# IMX425_MB.net
KiCad netlist of a schematic drawn in Altium Designer
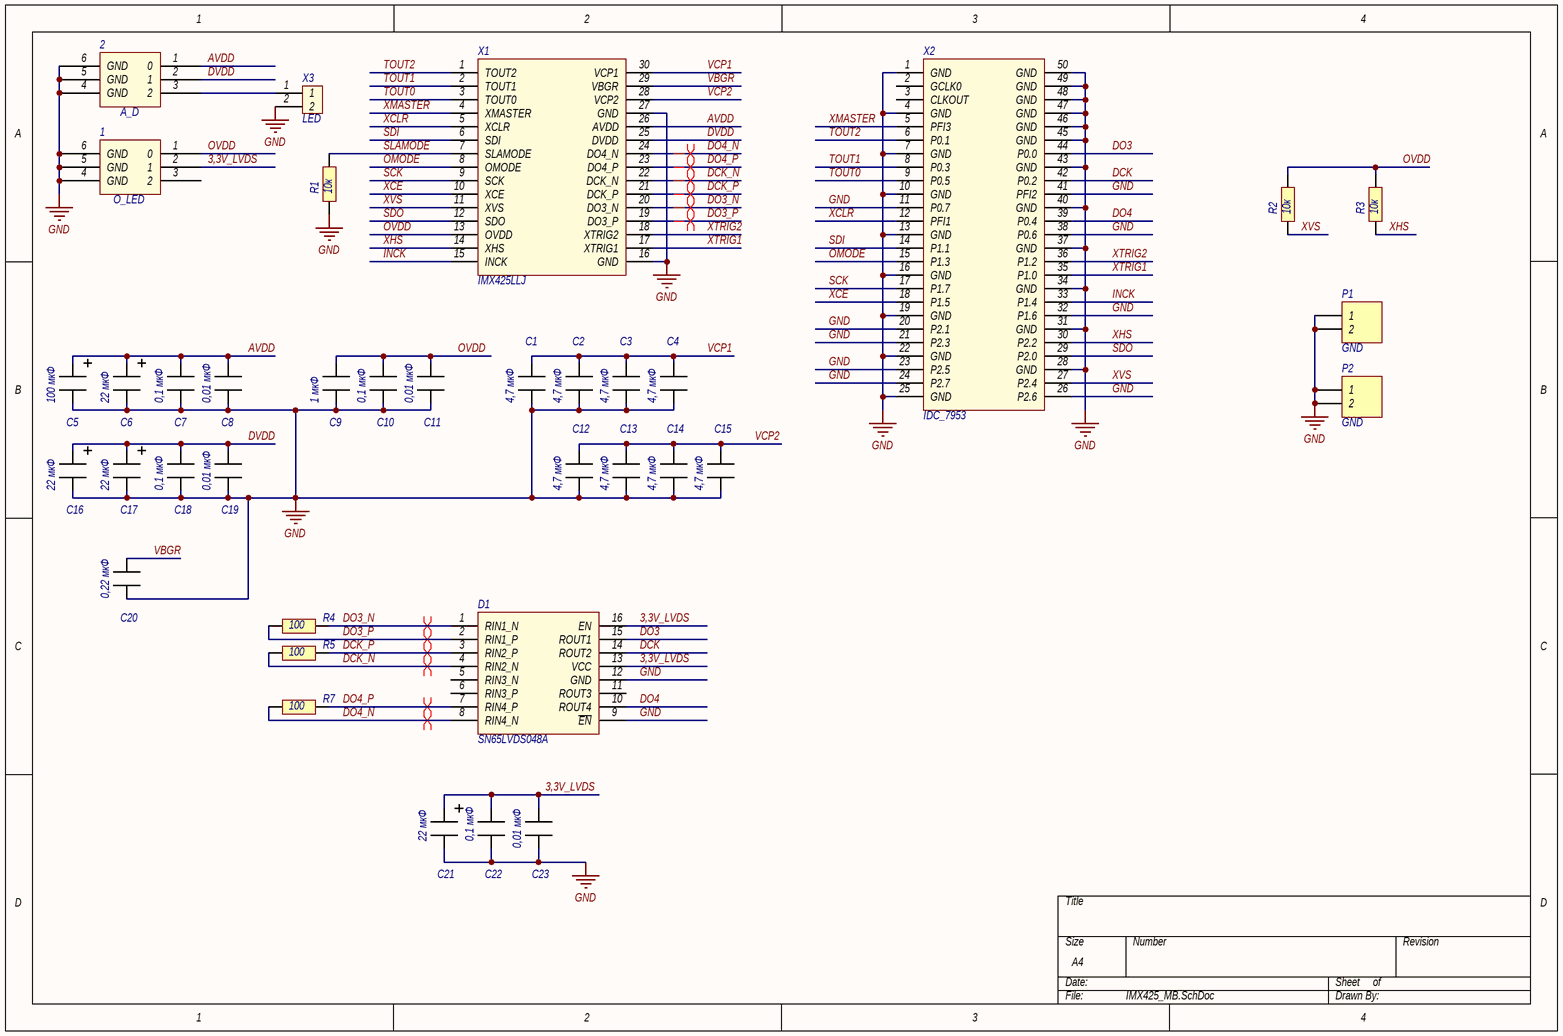
[diagram p0: IMX425_MB.SchDoc]

(export (version "E")
  (design (tool "Eeschema 10.0.6"))
  (components
    (comp (ref "1") (value "O_LED") (footprint "POWER") (libsource (lib "Schlib") (part "POWER")))
    (comp (ref "2") (value "A_D") (footprint "POWER") (libsource (lib "Schlib") (part "POWER")))
    (comp (ref "C1") (value "4,7 мкФ") (footprint "CAP_SMALL") (libsource (lib "Schlib") (part "CAP_SMALL")))
    (comp (ref "C2") (value "4,7 мкФ") (footprint "CAP_SMALL") (libsource (lib "Schlib") (part "CAP_SMALL")))
    (comp (ref "C3") (value "4,7 мкФ") (footprint "CAP_SMALL") (libsource (lib "Schlib") (part "CAP_SMALL")))
    (comp (ref "C4") (value "4,7 мкФ") (footprint "CAP_SMALL") (libsource (lib "Schlib") (part "CAP_SMALL")))
    (comp (ref "C5")
      (value "100 мкФ")
      (footprint "Cap_0612_electrolitic")
      (libsource (lib "Schlib") (part "Cap_electrolotoc_0612"))
    )
    (comp (ref "C6")
      (value "22 мкФ")
      (footprint "Cap_0511_electrolitic")
      (libsource (lib "Schlib") (part "Cap_electrolotoc_0511"))
    )
    (comp (ref "C7") (value "0,1 мкФ") (footprint "CAP_SMALL") (libsource (lib "Schlib") (part "CAP_SMALL")))
    (comp (ref "C8") (value "0,01 мкФ") (footprint "CAP_SMALL") (libsource (lib "Schlib") (part "CAP_SMALL")))
    (comp (ref "C9") (value "1 мкФ") (footprint "CAP_SMALL") (libsource (lib "Schlib") (part "CAP_SMALL")))
    (comp (ref "C10") (value "0,1 мкФ") (footprint "CAP_SMALL") (libsource (lib "Schlib") (part "CAP_SMALL")))
    (comp (ref "C11")
      (value "0,01 мкФ")
      (footprint "CAP_SMALL")
      (libsource (lib "Schlib") (part "CAP_SMALL"))
    )
    (comp (ref "C12") (value "4,7 мкФ") (footprint "CAP_SMALL") (libsource (lib "Schlib") (part "CAP_SMALL")))
    (comp (ref "C13") (value "4,7 мкФ") (footprint "CAP_SMALL") (libsource (lib "Schlib") (part "CAP_SMALL")))
    (comp (ref "C14") (value "4,7 мкФ") (footprint "CAP_SMALL") (libsource (lib "Schlib") (part "CAP_SMALL")))
    (comp (ref "C15") (value "4,7 мкФ") (footprint "CAP_SMALL") (libsource (lib "Schlib") (part "CAP_SMALL")))
    (comp (ref "C16")
      (value "22 мкФ")
      (footprint "Cap_0511_electrolitic")
      (libsource (lib "Schlib") (part "Cap_electrolotoc_0511"))
    )
    (comp (ref "C17")
      (value "22 мкФ")
      (footprint "Cap_0511_electrolitic")
      (libsource (lib "Schlib") (part "Cap_electrolotoc_0511"))
    )
    (comp (ref "C18") (value "0,1 мкФ") (footprint "CAP_SMALL") (libsource (lib "Schlib") (part "CAP_SMALL")))
    (comp (ref "C19")
      (value "0,01 мкФ")
      (footprint "CAP_SMALL")
      (libsource (lib "Schlib") (part "CAP_SMALL"))
    )
    (comp (ref "C20")
      (value "0,22 мкФ")
      (footprint "CAP_SMALL")
      (libsource (lib "Schlib") (part "CAP_SMALL"))
    )
    (comp (ref "C21")
      (value "22 мкФ")
      (footprint "Cap_0511_electrolitic")
      (libsource (lib "Schlib") (part "Cap_electrolotoc_0511"))
    )
    (comp (ref "C22") (value "0,1 мкФ") (footprint "CAP_SMALL") (libsource (lib "Schlib") (part "CAP_SMALL")))
    (comp (ref "C23")
      (value "0,01 мкФ")
      (footprint "CAP_SMALL")
      (libsource (lib "Schlib") (part "CAP_SMALL"))
    )
    (comp (ref "D1")
      (value "SN65LVDS048A")
      (footprint "SN65LVDS048A (4LVDS)")
      (libsource (lib "Schlib") (part "SN65LVDS048A (4LVDS)"))
    )
    (comp (ref "P1")
      (value "GND")
      (footprint "HDR1X2")
      (description "Header, 2-Pin")
      (fields (field (name "PUBLISHER") "Altium Limited"))
      (libsource (lib "Miscellaneous Connectors") (part "Header 2"))
    )
    (comp (ref "P2")
      (value "GND")
      (footprint "HDR1X2")
      (description "Header, 2-Pin")
      (fields (field (name "PUBLISHER") "Altium Limited"))
      (libsource (lib "Miscellaneous Connectors") (part "Header 2"))
    )
    (comp (ref "R1") (value "10к") (footprint "RES") (libsource (lib "Schlib") (part "RES")))
    (comp (ref "R2") (value "10к") (footprint "RES") (libsource (lib "Schlib") (part "RES")))
    (comp (ref "R3") (value "10к") (footprint "RES") (libsource (lib "Schlib") (part "RES")))
    (comp (ref "R4") (value "100") (footprint "RES") (libsource (lib "") (part "RES_1")))
    (comp (ref "R5") (value "100") (footprint "RES") (libsource (lib "") (part "RES_1")))
    (comp (ref "R7") (value "100") (footprint "RES") (libsource (lib "") (part "RES_1")))
    (comp (ref "X1")
      (value "IMX425LLJ")
      (footprint "IMX425LLJ_MEZ")
      (libsource (lib "VPL") (part "IMX425LLJ_MEZ"))
    )
    (comp (ref "X2") (value "IDC_7953") (footprint "IDC_7953") (libsource (lib "VPL") (part "IDC_7953")))
    (comp (ref "X3") (value "LED") (footprint "KLEMMNIK_2") (libsource (lib "Schlib") (part "KLEMMNIK_2")))
  )
  (nets
    (net (code "1") (name "/3,3V_LVDS") (class "Default")
      (node (ref "1") (pin "2") (pinfunction "1_2") (pintype "passive"))
      (node (ref "C21") (pin "1") (pinfunction "1_1") (pintype "passive"))
      (node (ref "C22") (pin "2") (pinfunction "2_2") (pintype "passive"))
      (node (ref "C23") (pin "2") (pinfunction "2_2") (pintype "passive"))
      (node (ref "D1") (pin "13") (pinfunction "VCC_13") (pintype "passive"))
      (node (ref "D1") (pin "16") (pinfunction "EN_16") (pintype "passive"))
    )
    (net (code "2") (name "/AVDD") (class "Default")
      (node (ref "2") (pin "1") (pinfunction "0_1") (pintype "passive"))
      (node (ref "C5") (pin "1") (pinfunction "1_1") (pintype "passive"))
      (node (ref "C6") (pin "1") (pinfunction "1_1") (pintype "passive"))
      (node (ref "C7") (pin "1") (pinfunction "1_1") (pintype "passive"))
      (node (ref "C8") (pin "1") (pinfunction "1_1") (pintype "passive"))
      (node (ref "X1") (pin "26") (pinfunction "AVDD_26") (pintype "passive"))
    )
    (net (code "3") (name "/DCK") (class "Default")
      (node (ref "D1") (pin "14") (pinfunction "ROUT2_14") (pintype "passive"))
      (node (ref "X2") (pin "42") (pinfunction "P0.2_42") (pintype "passive"))
    )
    (net (code "4") (name "/DCK_N") (class "Default")
      (node (ref "D1") (pin "4") (pinfunction "RIN2_N_4") (pintype "passive"))
      (node (ref "R5") (pin "2") (pinfunction "2_2") (pintype "passive"))
      (node (ref "X1") (pin "22") (pinfunction "DCK_N_22") (pintype "passive"))
    )
    (net (code "5") (name "/DCK_P") (class "Default")
      (node (ref "D1") (pin "3") (pinfunction "RIN2_P_3") (pintype "passive"))
      (node (ref "R5") (pin "1") (pinfunction "1_1") (pintype "passive"))
      (node (ref "X1") (pin "21") (pinfunction "DCK_P_21") (pintype "passive"))
    )
    (net (code "6") (name "/DO3") (class "Default")
      (node (ref "D1") (pin "15") (pinfunction "ROUT1_15") (pintype "passive"))
      (node (ref "X2") (pin "44") (pinfunction "P0.0_44") (pintype "passive"))
    )
    (net (code "7") (name "/DO3_N") (class "Default")
      (node (ref "D1") (pin "1") (pinfunction "RIN1_N_1") (pintype "passive"))
      (node (ref "R4") (pin "1") (pinfunction "1_1") (pintype "passive"))
      (node (ref "X1") (pin "20") (pinfunction "DO3_N_20") (pintype "passive"))
    )
    (net (code "8") (name "/DO3_P") (class "Default")
      (node (ref "D1") (pin "2") (pinfunction "RIN1_P_2") (pintype "passive"))
      (node (ref "R4") (pin "2") (pinfunction "2_2") (pintype "passive"))
      (node (ref "X1") (pin "19") (pinfunction "DO3_P_19") (pintype "passive"))
    )
    (net (code "9") (name "/DO4") (class "Default")
      (node (ref "D1") (pin "10") (pinfunction "ROUT4_10") (pintype "passive"))
      (node (ref "X2") (pin "39") (pinfunction "P0.4_39") (pintype "passive"))
    )
    (net (code "10") (name "/DO4_N") (class "Default")
      (node (ref "D1") (pin "8") (pinfunction "RIN4_N_8") (pintype "passive"))
      (node (ref "R7") (pin "2") (pinfunction "2_2") (pintype "passive"))
      (node (ref "X1") (pin "24") (pinfunction "DO4_N_24") (pintype "passive"))
    )
    (net (code "11") (name "/DO4_P") (class "Default")
      (node (ref "D1") (pin "7") (pinfunction "RIN4_P_7") (pintype "passive"))
      (node (ref "R7") (pin "1") (pinfunction "1_1") (pintype "passive"))
      (node (ref "X1") (pin "23") (pinfunction "DO4_P_23") (pintype "passive"))
    )
    (net (code "12") (name "/DVDD") (class "Default")
      (node (ref "2") (pin "2") (pinfunction "1_2") (pintype "passive"))
      (node (ref "C16") (pin "1") (pinfunction "1_1") (pintype "passive"))
      (node (ref "C17") (pin "1") (pinfunction "1_1") (pintype "passive"))
      (node (ref "C18") (pin "1") (pinfunction "1_1") (pintype "passive"))
      (node (ref "C19") (pin "1") (pinfunction "1_1") (pintype "passive"))
      (node (ref "X1") (pin "25") (pinfunction "DVDD_25") (pintype "passive"))
    )
    (net (code "13") (name "/INCK") (class "Default")
      (node (ref "X1") (pin "15") (pinfunction "INCK_15") (pintype "passive"))
      (node (ref "X2") (pin "33") (pinfunction "P1.4_33") (pintype "passive"))
    )
    (net (code "14") (name "/OMODE") (class "Default")
      (node (ref "X1") (pin "8") (pinfunction "OMODE_8") (pintype "passive"))
      (node (ref "X2") (pin "15") (pinfunction "P1.3_15") (pintype "passive"))
    )
    (net (code "15") (name "/OVDD") (class "Default")
      (node (ref "1") (pin "1") (pinfunction "0_1") (pintype "passive"))
      (node (ref "C10") (pin "1") (pinfunction "1_1") (pintype "passive"))
      (node (ref "C11") (pin "1") (pinfunction "1_1") (pintype "passive"))
      (node (ref "C9") (pin "1") (pinfunction "1_1") (pintype "passive"))
      (node (ref "R2") (pin "1") (pinfunction "1_1") (pintype "passive"))
      (node (ref "R3") (pin "1") (pinfunction "1_1") (pintype "passive"))
      (node (ref "X1") (pin "13") (pinfunction "OVDD_13") (pintype "passive"))
    )
    (net (code "16") (name "/SCK") (class "Default")
      (node (ref "X1") (pin "9") (pinfunction "SCK_9") (pintype "passive"))
      (node (ref "X2") (pin "17") (pinfunction "P1.7_17") (pintype "passive"))
    )
    (net (code "17") (name "/SDI") (class "Default")
      (node (ref "X1") (pin "6") (pinfunction "SDI_6") (pintype "passive"))
      (node (ref "X2") (pin "14") (pinfunction "P1.1_14") (pintype "passive"))
    )
    (net (code "18") (name "/SDO") (class "Default")
      (node (ref "X1") (pin "12") (pinfunction "SDO_12") (pintype "passive"))
      (node (ref "X2") (pin "29") (pinfunction "P2.0_29") (pintype "passive"))
    )
    (net (code "19") (name "/SLAMODE") (class "Default")
      (node (ref "R1") (pin "1") (pinfunction "1_1") (pintype "passive"))
      (node (ref "X1") (pin "7") (pinfunction "SLAMODE_7") (pintype "passive"))
    )
    (net (code "20") (name "/TOUT0") (class "Default")
      (node (ref "X1") (pin "3") (pinfunction "TOUT0_3") (pintype "passive"))
      (node (ref "X2") (pin "9") (pinfunction "P0.5_9") (pintype "passive"))
    )
    (net (code "21") (name "/TOUT1") (class "Default")
      (node (ref "X1") (pin "2") (pinfunction "TOUT1_2") (pintype "passive"))
      (node (ref "X2") (pin "8") (pinfunction "P0.3_8") (pintype "passive"))
    )
    (net (code "22") (name "/TOUT2") (class "Default")
      (node (ref "X1") (pin "1") (pinfunction "TOUT2_1") (pintype "passive"))
      (node (ref "X2") (pin "6") (pinfunction "P0.1_6") (pintype "passive"))
    )
    (net (code "23") (name "/VBGR") (class "Default")
      (node (ref "C20") (pin "1") (pinfunction "1_1") (pintype "passive"))
      (node (ref "X1") (pin "29") (pinfunction "VBGR_29") (pintype "passive"))
    )
    (net (code "24") (name "/VCP1") (class "Default")
      (node (ref "C1") (pin "1") (pinfunction "1_1") (pintype "passive"))
      (node (ref "C2") (pin "1") (pinfunction "1_1") (pintype "passive"))
      (node (ref "C3") (pin "1") (pinfunction "1_1") (pintype "passive"))
      (node (ref "C4") (pin "1") (pinfunction "1_1") (pintype "passive"))
      (node (ref "X1") (pin "30") (pinfunction "VCP1_30") (pintype "passive"))
    )
    (net (code "25") (name "/VCP2") (class "Default")
      (node (ref "C12") (pin "1") (pinfunction "1_1") (pintype "passive"))
      (node (ref "C13") (pin "1") (pinfunction "1_1") (pintype "passive"))
      (node (ref "C14") (pin "1") (pinfunction "1_1") (pintype "passive"))
      (node (ref "C15") (pin "1") (pinfunction "1_1") (pintype "passive"))
      (node (ref "X1") (pin "28") (pinfunction "VCP2_28") (pintype "passive"))
    )
    (net (code "26") (name "/XCE") (class "Default")
      (node (ref "X1") (pin "10") (pinfunction "XCE_10") (pintype "passive"))
      (node (ref "X2") (pin "18") (pinfunction "P1.5_18") (pintype "passive"))
    )
    (net (code "27") (name "/XCLR") (class "Default")
      (node (ref "X1") (pin "5") (pinfunction "XCLR_5") (pintype "passive"))
      (node (ref "X2") (pin "12") (pinfunction "PFI1_12") (pintype "passive"))
    )
    (net (code "28") (name "/XHS") (class "Default")
      (node (ref "R3") (pin "2") (pinfunction "2_2") (pintype "passive"))
      (node (ref "X1") (pin "14") (pinfunction "XHS_14") (pintype "passive"))
      (node (ref "X2") (pin "30") (pinfunction "P2.2_30") (pintype "passive"))
    )
    (net (code "29") (name "/XMASTER") (class "Default")
      (node (ref "X1") (pin "4") (pinfunction "XMASTER_4") (pintype "passive"))
      (node (ref "X2") (pin "5") (pinfunction "PFI3_5") (pintype "passive"))
    )
    (net (code "30") (name "/XTRIG1") (class "Default")
      (node (ref "X1") (pin "17") (pinfunction "XTRIG1_17") (pintype "passive"))
      (node (ref "X2") (pin "35") (pinfunction "P1.0_35") (pintype "passive"))
    )
    (net (code "31") (name "/XTRIG2") (class "Default")
      (node (ref "X1") (pin "18") (pinfunction "XTRIG2_18") (pintype "passive"))
      (node (ref "X2") (pin "36") (pinfunction "P1.2_36") (pintype "passive"))
    )
    (net (code "32") (name "/XVS") (class "Default")
      (node (ref "R2") (pin "2") (pinfunction "2_2") (pintype "passive"))
      (node (ref "X1") (pin "11") (pinfunction "XVS_11") (pintype "passive"))
      (node (ref "X2") (pin "27") (pinfunction "P2.4_27") (pintype "passive"))
    )
    (net (code "33") (name "GND") (class "Default")
      (node (ref "1") (pin "4") (pinfunction "GND_4") (pintype "passive"))
      (node (ref "1") (pin "5") (pinfunction "GND_5") (pintype "passive"))
      (node (ref "1") (pin "6") (pinfunction "GND_6") (pintype "passive"))
      (node (ref "2") (pin "4") (pinfunction "GND_4") (pintype "passive"))
      (node (ref "2") (pin "5") (pinfunction "GND_5") (pintype "passive"))
      (node (ref "2") (pin "6") (pinfunction "GND_6") (pintype "passive"))
      (node (ref "C1") (pin "2") (pinfunction "2_2") (pintype "passive"))
      (node (ref "C10") (pin "2") (pinfunction "2_2") (pintype "passive"))
      (node (ref "C11") (pin "2") (pinfunction "2_2") (pintype "passive"))
      (node (ref "C12") (pin "2") (pinfunction "2_2") (pintype "passive"))
      (node (ref "C13") (pin "2") (pinfunction "2_2") (pintype "passive"))
      (node (ref "C14") (pin "2") (pinfunction "2_2") (pintype "passive"))
      (node (ref "C15") (pin "2") (pinfunction "2_2") (pintype "passive"))
      (node (ref "C16") (pin "2") (pinfunction "2_2") (pintype "passive"))
      (node (ref "C17") (pin "2") (pinfunction "2_2") (pintype "passive"))
      (node (ref "C18") (pin "2") (pinfunction "2_2") (pintype "passive"))
      (node (ref "C19") (pin "2") (pinfunction "2_2") (pintype "passive"))
      (node (ref "C2") (pin "2") (pinfunction "2_2") (pintype "passive"))
      (node (ref "C20") (pin "2") (pinfunction "2_2") (pintype "passive"))
      (node (ref "C21") (pin "2") (pinfunction "2_2") (pintype "passive"))
      (node (ref "C22") (pin "1") (pinfunction "1_1") (pintype "passive"))
      (node (ref "C23") (pin "1") (pinfunction "1_1") (pintype "passive"))
      (node (ref "C3") (pin "2") (pinfunction "2_2") (pintype "passive"))
      (node (ref "C4") (pin "2") (pinfunction "2_2") (pintype "passive"))
      (node (ref "C5") (pin "2") (pinfunction "2_2") (pintype "passive"))
      (node (ref "C6") (pin "2") (pinfunction "2_2") (pintype "passive"))
      (node (ref "C7") (pin "2") (pinfunction "2_2") (pintype "passive"))
      (node (ref "C8") (pin "2") (pinfunction "2_2") (pintype "passive"))
      (node (ref "C9") (pin "2") (pinfunction "2_2") (pintype "passive"))
      (node (ref "D1") (pin "12") (pinfunction "GND_12") (pintype "passive"))
      (node (ref "D1") (pin "9") (pinfunction "~{EN}_9") (pintype "passive"))
      (node (ref "P1") (pin "1") (pinfunction "1_1") (pintype "passive"))
      (node (ref "P1") (pin "2") (pinfunction "2_2") (pintype "passive"))
      (node (ref "P2") (pin "1") (pinfunction "1_1") (pintype "passive"))
      (node (ref "P2") (pin "2") (pinfunction "2_2") (pintype "passive"))
      (node (ref "R1") (pin "2") (pinfunction "2_2") (pintype "passive"))
      (node (ref "X1") (pin "16") (pinfunction "GND_16") (pintype "passive"))
      (node (ref "X1") (pin "27") (pinfunction "GND_27") (pintype "passive"))
      (node (ref "X2") (pin "1") (pinfunction "GND_1") (pintype "passive"))
      (node (ref "X2") (pin "10") (pinfunction "GND_10") (pintype "passive"))
      (node (ref "X2") (pin "11") (pinfunction "P0.7_11") (pintype "passive"))
      (node (ref "X2") (pin "13") (pinfunction "GND_13") (pintype "passive"))
      (node (ref "X2") (pin "16") (pinfunction "GND_16") (pintype "passive"))
      (node (ref "X2") (pin "19") (pinfunction "GND_19") (pintype "passive"))
      (node (ref "X2") (pin "20") (pinfunction "P2.1_20") (pintype "passive"))
      (node (ref "X2") (pin "21") (pinfunction "P2.3_21") (pintype "passive"))
      (node (ref "X2") (pin "22") (pinfunction "GND_22") (pintype "passive"))
      (node (ref "X2") (pin "23") (pinfunction "P2.5_23") (pintype "passive"))
      (node (ref "X2") (pin "24") (pinfunction "P2.7_24") (pintype "passive"))
      (node (ref "X2") (pin "25") (pinfunction "GND_25") (pintype "passive"))
      (node (ref "X2") (pin "26") (pinfunction "P2.6_26") (pintype "passive"))
      (node (ref "X2") (pin "28") (pinfunction "GND_28") (pintype "passive"))
      (node (ref "X2") (pin "31") (pinfunction "GND_31") (pintype "passive"))
      (node (ref "X2") (pin "32") (pinfunction "P1.6_32") (pintype "passive"))
      (node (ref "X2") (pin "34") (pinfunction "GND_34") (pintype "passive"))
      (node (ref "X2") (pin "37") (pinfunction "GND_37") (pintype "passive"))
      (node (ref "X2") (pin "38") (pinfunction "P0.6_38") (pintype "passive"))
      (node (ref "X2") (pin "4") (pinfunction "GND_4") (pintype "passive"))
      (node (ref "X2") (pin "40") (pinfunction "GND_40") (pintype "passive"))
      (node (ref "X2") (pin "41") (pinfunction "PFI2_41") (pintype "passive"))
      (node (ref "X2") (pin "43") (pinfunction "GND_43") (pintype "passive"))
      (node (ref "X2") (pin "45") (pinfunction "GND_45") (pintype "passive"))
      (node (ref "X2") (pin "46") (pinfunction "GND_46") (pintype "passive"))
      (node (ref "X2") (pin "47") (pinfunction "GND_47") (pintype "passive"))
      (node (ref "X2") (pin "48") (pinfunction "GND_48") (pintype "passive"))
      (node (ref "X2") (pin "49") (pinfunction "GND_49") (pintype "passive"))
      (node (ref "X2") (pin "50") (pinfunction "GND_50") (pintype "passive"))
      (node (ref "X2") (pin "7") (pinfunction "GND_7") (pintype "passive"))
      (node (ref "X3") (pin "2") (pinfunction "2_2") (pintype "passive"))
    )
    (net (code "34") (name "Net-(2-2)") (class "Default")
      (node (ref "2") (pin "3") (pinfunction "2_3") (pintype "passive"))
      (node (ref "X3") (pin "1") (pinfunction "1_1") (pintype "passive"))
    )
    (net (code "35") (name "unconnected-(1-2-Pad3)") (class "Default")
      (node (ref "1") (pin "3") (pinfunction "2_3") (pintype "passive"))
    )
    (net (code "36") (name "unconnected-(D1-RIN3_N-Pad5)") (class "Default")
      (node (ref "D1") (pin "5") (pinfunction "RIN3_N_5") (pintype "passive"))
    )
    (net (code "37") (name "unconnected-(D1-RIN3_P-Pad6)") (class "Default")
      (node (ref "D1") (pin "6") (pinfunction "RIN3_P_6") (pintype "passive"))
    )
    (net (code "38") (name "unconnected-(D1-ROUT3-Pad11)") (class "Default")
      (node (ref "D1") (pin "11") (pinfunction "ROUT3_11") (pintype "passive"))
    )
    (net (code "39") (name "unconnected-(X2-CLKOUT-Pad3)") (class "Default")
      (node (ref "X2") (pin "3") (pinfunction "CLKOUT_3") (pintype "passive"))
    )
    (net (code "40") (name "unconnected-(X2-GCLK0-Pad2)") (class "Default")
      (node (ref "X2") (pin "2") (pinfunction "GCLK0_2") (pintype "passive"))
    )
  )
)
